# Driver.net
KiCad netlist of a schematic drawn in Altium Designer
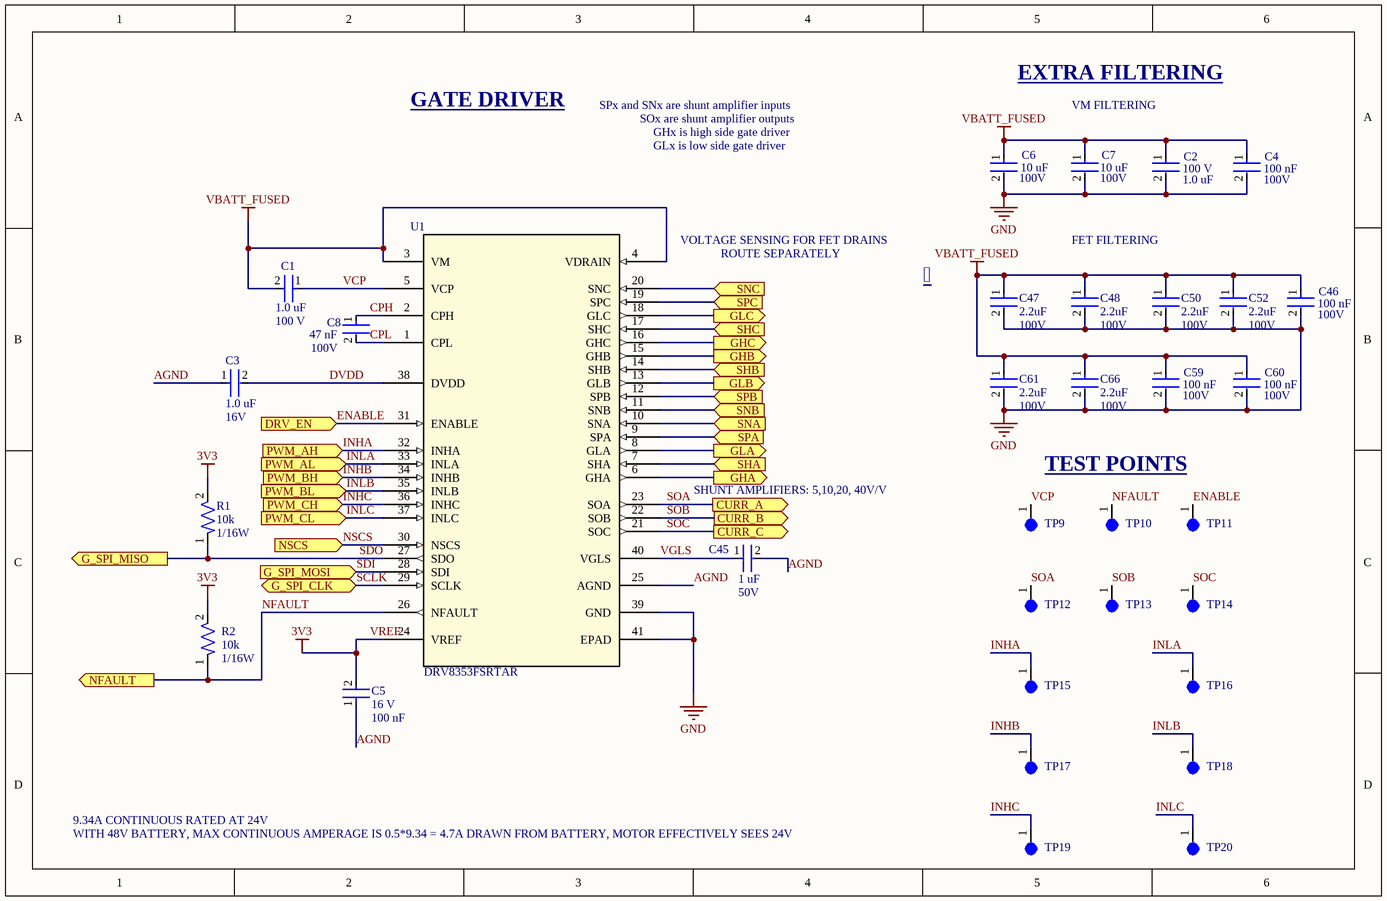
[diagram p0: Driver.SchDoc]

(export (version "E")
  (design (tool "Eeschema 10.0.6"))
  (components
    (comp (ref "C1")
      (value "08051C105K4Z2A")
      (footprint "CAP-0805")
      (description "CAP CER 1UF 50V X7R 0805")
      (fields (field (name "VOLTAGE") "100 V") (field (name "CAPACITANCE") "1.0 uF"))
      (libsource (lib "JLC_25") (part "CAP-1U-0001"))
    )
    (comp (ref "C2")
      (value "08051C105K4Z2A")
      (footprint "CAP-0805")
      (description "CAP CER 1UF 50V X7R 0805")
      (fields (field (name "VOLTAGE") "100 V") (field (name "CAPACITANCE") "1.0 uF"))
      (libsource (lib "JLC_25") (part "CAP-1U-0001"))
    )
    (comp (ref "C3")
      (value "CC0603KRX7R7BB105")
      (footprint "CAP-0603")
      (description "CAP CER 1UF 16V X7R 0603")
      (fields (field (name "CAPACITANCE") "1.0 uF") (field (name "VOLTAGE") "16V"))
      (libsource (lib "JLC_25") (part "CAP-1U-0002"))
    )
    (comp (ref "C4")
      (value "GRM188R72A104KA35D")
      (footprint "CAP-0603")
      (description "CAP CER 100NF 100V X7R 0603")
      (fields (field (name "CAPACITANCE") "100 nF") (field (name "VOLTAGE") "100V"))
      (libsource (lib "JLC_25") (part "CAP-1U-0002"))
    )
    (comp (ref "C5")
      (value "CC0402KRX7R7BB104")
      (footprint "CAP-0402")
      (description "CAP CER 0.1UF 16V X7R 0402")
      (fields (field (name "VOLTAGE RATING") "16 V") (field (name "CAPACITANCE") "100 nF"))
      (libsource (lib "JLC_25") (part "CAP-0.1U-0001"))
    )
    (comp (ref "C6")
      (value "GRM32EC72A106KE05L")
      (footprint "CAP-1210")
      (description "10 µF ±10% 100V Ceramic Capacitor X7S 1210 (3225 Metric)")
      (fields (field (name "CAPCITANCE") "10 uF") (field (name "VOLTAGE RATING") "100V"))
      (libsource (lib "MasterLib") (part "CAP-10U-0003"))
    )
    (comp (ref "C7")
      (value "GRM32EC72A106KE05L")
      (footprint "CAP-1210")
      (description "10 µF ±10% 100V Ceramic Capacitor X7S 1210 (3225 Metric)")
      (fields (field (name "CAPCITANCE") "10 uF") (field (name "VOLTAGE RATING") "100V"))
      (libsource (lib "MasterLib") (part "CAP-10U-0003"))
    )
    (comp (ref "C8")
      (value "C0603C473K1RACTU")
      (footprint "CAP-0603")
      (description "CAP CER 47NF 100V X5R 0603")
      (fields (field (name "CAPACITANCE") "47 nF") (field (name "VOLTAGE") "100V"))
      (libsource (lib "JLC_25") (part "CAP-4.7U-0001"))
    )
    (comp (ref "C45")
      (value "UMK107AB7105KA-T")
      (footprint "CAP-0603")
      (description "1 µF ±10% 50V Ceramic Capacitor X7R 0603 (1608 Metric)")
      (fields (field (name "CAPACITANCE") "1 uF") (field (name "VOLTAGE") "50V"))
      (libsource (lib "MasterLib") (part "CAP-1U-0002"))
    )
    (comp (ref "C46")
      (value "GRM188R72A104KA35D")
      (footprint "CAP-0603")
      (description "CAP CER 100NF 100V X7R 0603")
      (fields (field (name "CAPACITANCE") "100 nF") (field (name "VOLTAGE") "100V"))
      (libsource (lib "JLC_25") (part "CAP-1U-0002"))
    )
    (comp (ref "C47")
      (value "CC1206KKX7R0BB225")
      (footprint "CAP-1206")
      (description "CAP CER 2.2UF 100V X7R 1206")
      (fields (field (name "CAPACITANCE") "2.2uF") (field (name "VOLTAGE") "100V"))
      (libsource (lib "JLC_25") (part "CAP-2.2U-0001"))
    )
    (comp (ref "C48")
      (value "CC1206KKX7R0BB225")
      (footprint "CAP-1206")
      (description "CAP CER 2.2UF 100V X7R 1206")
      (fields (field (name "CAPACITANCE") "2.2uF") (field (name "VOLTAGE") "100V"))
      (libsource (lib "JLC_25") (part "CAP-2.2U-0001"))
    )
    (comp (ref "C50")
      (value "CC1206KKX7R0BB225")
      (footprint "CAP-1206")
      (description "CAP CER 2.2UF 100V X7R 1206")
      (fields (field (name "CAPACITANCE") "2.2uF") (field (name "VOLTAGE") "100V"))
      (libsource (lib "JLC_25") (part "CAP-2.2U-0001"))
    )
    (comp (ref "C52")
      (value "CC1206KKX7R0BB225")
      (footprint "CAP-1206")
      (description "CAP CER 2.2UF 100V X7R 1206")
      (fields (field (name "CAPACITANCE") "2.2uF") (field (name "VOLTAGE") "100V"))
      (libsource (lib "JLC_25") (part "CAP-2.2U-0001"))
    )
    (comp (ref "C59")
      (value "GRM188R72A104KA35D")
      (footprint "CAP-0603")
      (description "CAP CER 100NF 100V X7R 0603")
      (fields (field (name "CAPACITANCE") "100 nF") (field (name "VOLTAGE") "100V"))
      (libsource (lib "JLC_25") (part "CAP-1U-0002"))
    )
    (comp (ref "C60")
      (value "GRM188R72A104KA35D")
      (footprint "CAP-0603")
      (description "CAP CER 100NF 100V X7R 0603")
      (fields (field (name "CAPACITANCE") "100 nF") (field (name "VOLTAGE") "100V"))
      (libsource (lib "JLC_25") (part "CAP-1U-0002"))
    )
    (comp (ref "C61")
      (value "CC1206KKX7R0BB225")
      (footprint "CAP-1206")
      (description "CAP CER 2.2UF 100V X7R 1206")
      (fields (field (name "CAPACITANCE") "2.2uF") (field (name "VOLTAGE") "100V"))
      (libsource (lib "JLC_25") (part "CAP-2.2U-0001"))
    )
    (comp (ref "C66")
      (value "CC1206KKX7R0BB225")
      (footprint "CAP-1206")
      (description "CAP CER 2.2UF 100V X7R 1206")
      (fields (field (name "CAPACITANCE") "2.2uF") (field (name "VOLTAGE") "100V"))
      (libsource (lib "JLC_25") (part "CAP-2.2U-0001"))
    )
    (comp (ref "R1")
      (value "RC0402FR-0710KL")
      (footprint "RES-0402")
      (description "RES 10K OHM 1% 1/16W 0402")
      (fields
        (field (name "TOLERANCE") "1%")
        (field (name "RESISTANCE") "10k")
        (field (name "POWER") "1/16W")
      )
      (libsource (lib "JLC_25") (part "RES-10k-0001"))
    )
    (comp (ref "R2")
      (value "RC0402FR-0710KL")
      (footprint "RES-0402")
      (description "RES 10K OHM 1% 1/16W 0402")
      (fields
        (field (name "TOLERANCE") "1%")
        (field (name "RESISTANCE") "10k")
        (field (name "POWER") "1/16W")
      )
      (libsource (lib "JLC_25") (part "RES-10k-0001"))
    )
    (comp (ref "TP9")
      (value "5003")
      (footprint "TEST-POINT-0001")
      (description "Oranange PC Test Point, Miniature Phoisphor Bronze Silver Plating Through Hole Mounting Type")
      (libsource (lib "JLC_25") (part "TEST-POINT-0001"))
    )
    (comp (ref "TP10")
      (value "5003")
      (footprint "TEST-POINT-0001")
      (description "Oranange PC Test Point, Miniature Phoisphor Bronze Silver Plating Through Hole Mounting Type")
      (libsource (lib "JLC_25") (part "TEST-POINT-0001"))
    )
    (comp (ref "TP11")
      (value "5003")
      (footprint "TEST-POINT-0001")
      (description "Oranange PC Test Point, Miniature Phoisphor Bronze Silver Plating Through Hole Mounting Type")
      (libsource (lib "JLC_25") (part "TEST-POINT-0001"))
    )
    (comp (ref "TP12")
      (value "5003")
      (footprint "TEST-POINT-0001")
      (description "Oranange PC Test Point, Miniature Phoisphor Bronze Silver Plating Through Hole Mounting Type")
      (libsource (lib "JLC_25") (part "TEST-POINT-0001"))
    )
    (comp (ref "TP13")
      (value "5003")
      (footprint "TEST-POINT-0001")
      (description "Oranange PC Test Point, Miniature Phoisphor Bronze Silver Plating Through Hole Mounting Type")
      (libsource (lib "JLC_25") (part "TEST-POINT-0001"))
    )
    (comp (ref "TP14")
      (value "5003")
      (footprint "TEST-POINT-0001")
      (description "Oranange PC Test Point, Miniature Phoisphor Bronze Silver Plating Through Hole Mounting Type")
      (libsource (lib "JLC_25") (part "TEST-POINT-0001"))
    )
    (comp (ref "TP15")
      (value "5003")
      (footprint "TEST-POINT-0001")
      (description "Oranange PC Test Point, Miniature Phoisphor Bronze Silver Plating Through Hole Mounting Type")
      (libsource (lib "JLC_25") (part "TEST-POINT-0001"))
    )
    (comp (ref "TP16")
      (value "5003")
      (footprint "TEST-POINT-0001")
      (description "Oranange PC Test Point, Miniature Phoisphor Bronze Silver Plating Through Hole Mounting Type")
      (libsource (lib "JLC_25") (part "TEST-POINT-0001"))
    )
    (comp (ref "TP17")
      (value "5003")
      (footprint "TEST-POINT-0001")
      (description "Oranange PC Test Point, Miniature Phoisphor Bronze Silver Plating Through Hole Mounting Type")
      (libsource (lib "JLC_25") (part "TEST-POINT-0001"))
    )
    (comp (ref "TP18")
      (value "5003")
      (footprint "TEST-POINT-0001")
      (description "Oranange PC Test Point, Miniature Phoisphor Bronze Silver Plating Through Hole Mounting Type")
      (libsource (lib "JLC_25") (part "TEST-POINT-0001"))
    )
    (comp (ref "TP19")
      (value "5003")
      (footprint "TEST-POINT-0001")
      (description "Oranange PC Test Point, Miniature Phoisphor Bronze Silver Plating Through Hole Mounting Type")
      (libsource (lib "JLC_25") (part "TEST-POINT-0001"))
    )
    (comp (ref "TP20")
      (value "5003")
      (footprint "TEST-POINT-0001")
      (description "Oranange PC Test Point, Miniature Phoisphor Bronze Silver Plating Through Hole Mounting Type")
      (libsource (lib "JLC_25") (part "TEST-POINT-0001"))
    )
    (comp (ref "U1")
      (value "DRV8353FSRTAR")
      (footprint "IC-GDRV-0002")
      (description "102-V MAX 3-PHASE FUNCTIONAL SAF")
      (fields (field (name "COPYRIGHT") "Copyright (C) 2025 Ultra Librarian. All rights reserved."))
      (libsource (lib "MasterLib") (part "IC-GDRV-0002"))
    )
  )
  (nets
    (net (code "1") (name "/AGND") (class "Default")
      (node (ref "C3") (pin "1") (pinfunction "1_1") (pintype "passive"))
      (node (ref "C45") (pin "2") (pinfunction "2_2") (pintype "passive"))
      (node (ref "C5") (pin "1") (pinfunction "1_1") (pintype "passive"))
      (node (ref "U1") (pin "25") (pinfunction "AGND_25") (pintype "power_in"))
    )
    (net (code "2") (name "/CPH") (class "Default")
      (node (ref "C8") (pin "1") (pinfunction "1_1") (pintype "passive"))
      (node (ref "U1") (pin "2") (pinfunction "CPH_2") (pintype "power_in"))
    )
    (net (code "3") (name "/CPL") (class "Default")
      (node (ref "C8") (pin "2") (pinfunction "2_2") (pintype "passive"))
      (node (ref "U1") (pin "1") (pinfunction "CPL_1") (pintype "power_in"))
    )
    (net (code "4") (name "/DVDD") (class "Default")
      (node (ref "C3") (pin "2") (pinfunction "2_2") (pintype "passive"))
      (node (ref "U1") (pin "38") (pinfunction "DVDD_38") (pintype "power_in"))
    )
    (net (code "5") (name "/ENABLE") (class "Default")
      (node (ref "TP11") (pin "1") (pinfunction "0_1") (pintype "passive"))
      (node (ref "U1") (pin "31") (pinfunction "ENABLE_31") (pintype "input"))
    )
    (net (code "6") (name "/GHA") (class "Default")
      (node (ref "U1") (pin "6") (pinfunction "GHA_6") (pintype "output"))
    )
    (net (code "7") (name "/GHB") (class "Default")
      (node (ref "U1") (pin "15") (pinfunction "GHB_15") (pintype "output"))
    )
    (net (code "8") (name "/GHC") (class "Default")
      (node (ref "U1") (pin "16") (pinfunction "GHC_16") (pintype "output"))
    )
    (net (code "9") (name "/GLA") (class "Default")
      (node (ref "U1") (pin "8") (pinfunction "GLA_8") (pintype "output"))
    )
    (net (code "10") (name "/GLB") (class "Default")
      (node (ref "U1") (pin "13") (pinfunction "GLB_13") (pintype "output"))
    )
    (net (code "11") (name "/GLC") (class "Default")
      (node (ref "U1") (pin "18") (pinfunction "GLC_18") (pintype "output"))
    )
    (net (code "12") (name "/INHA") (class "Default")
      (node (ref "TP15") (pin "1") (pinfunction "0_1") (pintype "passive"))
      (node (ref "U1") (pin "32") (pinfunction "INHA_32") (pintype "input"))
    )
    (net (code "13") (name "/INHB") (class "Default")
      (node (ref "TP17") (pin "1") (pinfunction "0_1") (pintype "passive"))
      (node (ref "U1") (pin "34") (pinfunction "INHB_34") (pintype "input"))
    )
    (net (code "14") (name "/INHC") (class "Default")
      (node (ref "TP19") (pin "1") (pinfunction "0_1") (pintype "passive"))
      (node (ref "U1") (pin "36") (pinfunction "INHC_36") (pintype "input"))
    )
    (net (code "15") (name "/INLA") (class "Default")
      (node (ref "TP16") (pin "1") (pinfunction "0_1") (pintype "passive"))
      (node (ref "U1") (pin "33") (pinfunction "INLA_33") (pintype "input"))
    )
    (net (code "16") (name "/INLB") (class "Default")
      (node (ref "TP18") (pin "1") (pinfunction "0_1") (pintype "passive"))
      (node (ref "U1") (pin "35") (pinfunction "INLB_35") (pintype "input"))
    )
    (net (code "17") (name "/INLC") (class "Default")
      (node (ref "TP20") (pin "1") (pinfunction "0_1") (pintype "passive"))
      (node (ref "U1") (pin "37") (pinfunction "INLC_37") (pintype "input"))
    )
    (net (code "18") (name "/NFAULT") (class "Default")
      (node (ref "R2") (pin "1") (pinfunction "1_1") (pintype "passive"))
      (node (ref "TP10") (pin "1") (pinfunction "0_1") (pintype "passive"))
      (node (ref "U1") (pin "26") (pinfunction "NFAULT_26") (pintype "output"))
    )
    (net (code "19") (name "/NSCS") (class "Default")
      (node (ref "U1") (pin "30") (pinfunction "NSCS_30") (pintype "input"))
    )
    (net (code "20") (name "/SCLK") (class "Default")
      (node (ref "U1") (pin "29") (pinfunction "SCLK_29") (pintype "input"))
    )
    (net (code "21") (name "/SDI") (class "Default")
      (node (ref "U1") (pin "28") (pinfunction "SDI_28") (pintype "input"))
    )
    (net (code "22") (name "/SDO") (class "Default")
      (node (ref "R1") (pin "1") (pinfunction "1_1") (pintype "passive"))
      (node (ref "U1") (pin "27") (pinfunction "SDO_27") (pintype "output"))
    )
    (net (code "23") (name "/SHA") (class "Default")
      (node (ref "U1") (pin "7") (pinfunction "SHA_7") (pintype "input"))
    )
    (net (code "24") (name "/SHB") (class "Default")
      (node (ref "U1") (pin "14") (pinfunction "SHB_14") (pintype "input"))
    )
    (net (code "25") (name "/SHC") (class "Default")
      (node (ref "U1") (pin "17") (pinfunction "SHC_17") (pintype "input"))
    )
    (net (code "26") (name "/SNA") (class "Default")
      (node (ref "U1") (pin "10") (pinfunction "SNA_10") (pintype "input"))
    )
    (net (code "27") (name "/SNB") (class "Default")
      (node (ref "U1") (pin "11") (pinfunction "SNB_11") (pintype "input"))
    )
    (net (code "28") (name "/SNC") (class "Default")
      (node (ref "U1") (pin "20") (pinfunction "SNC_20") (pintype "input"))
    )
    (net (code "29") (name "/SOA") (class "Default")
      (node (ref "TP12") (pin "1") (pinfunction "0_1") (pintype "passive"))
      (node (ref "U1") (pin "23") (pinfunction "SOA_23") (pintype "output"))
    )
    (net (code "30") (name "/SOB") (class "Default")
      (node (ref "TP13") (pin "1") (pinfunction "0_1") (pintype "passive"))
      (node (ref "U1") (pin "22") (pinfunction "SOB_22") (pintype "output"))
    )
    (net (code "31") (name "/SOC") (class "Default")
      (node (ref "TP14") (pin "1") (pinfunction "0_1") (pintype "passive"))
      (node (ref "U1") (pin "21") (pinfunction "SOC_21") (pintype "output"))
    )
    (net (code "32") (name "/SPA") (class "Default")
      (node (ref "U1") (pin "9") (pinfunction "SPA_9") (pintype "input"))
    )
    (net (code "33") (name "/SPB") (class "Default")
      (node (ref "U1") (pin "12") (pinfunction "SPB_12") (pintype "input"))
    )
    (net (code "34") (name "/SPC") (class "Default")
      (node (ref "U1") (pin "19") (pinfunction "SPC_19") (pintype "input"))
    )
    (net (code "35") (name "/VCP") (class "Default")
      (node (ref "C1") (pin "1") (pinfunction "1_1") (pintype "passive"))
      (node (ref "TP9") (pin "1") (pinfunction "0_1") (pintype "passive"))
      (node (ref "U1") (pin "5") (pinfunction "VCP_5") (pintype "power_in"))
    )
    (net (code "36") (name "/VGLS") (class "Default")
      (node (ref "C45") (pin "1") (pinfunction "1_1") (pintype "passive"))
      (node (ref "U1") (pin "40") (pinfunction "VGLS_40") (pintype "power_in"))
    )
    (net (code "37") (name "3V3") (class "Default")
      (node (ref "C5") (pin "2") (pinfunction "2_2") (pintype "passive"))
      (node (ref "R1") (pin "2") (pinfunction "2_2") (pintype "passive"))
      (node (ref "R2") (pin "2") (pinfunction "2_2") (pintype "passive"))
      (node (ref "U1") (pin "24") (pinfunction "VREF_24") (pintype "power_in"))
    )
    (net (code "38") (name "GND") (class "Default")
      (node (ref "C2") (pin "2") (pinfunction "2_2") (pintype "passive"))
      (node (ref "C4") (pin "2") (pinfunction "2_2") (pintype "passive"))
      (node (ref "C46") (pin "2") (pinfunction "2_2") (pintype "passive"))
      (node (ref "C47") (pin "2") (pinfunction "2_2") (pintype "passive"))
      (node (ref "C48") (pin "2") (pinfunction "2_2") (pintype "passive"))
      (node (ref "C50") (pin "2") (pinfunction "2_2") (pintype "passive"))
      (node (ref "C52") (pin "2") (pinfunction "2_2") (pintype "passive"))
      (node (ref "C59") (pin "2") (pinfunction "2_2") (pintype "passive"))
      (node (ref "C6") (pin "2") (pinfunction "2_2") (pintype "passive"))
      (node (ref "C60") (pin "2") (pinfunction "2_2") (pintype "passive"))
      (node (ref "C61") (pin "2") (pinfunction "2_2") (pintype "passive"))
      (node (ref "C66") (pin "2") (pinfunction "2_2") (pintype "passive"))
      (node (ref "C7") (pin "2") (pinfunction "2_2") (pintype "passive"))
      (node (ref "U1") (pin "39") (pinfunction "GND_39") (pintype "power_in"))
      (node (ref "U1") (pin "41") (pinfunction "EPAD_41") (pintype "power_in"))
    )
    (net (code "39") (name "VBATT_FUSED") (class "Default")
      (node (ref "C1") (pin "2") (pinfunction "2_2") (pintype "passive"))
      (node (ref "C2") (pin "1") (pinfunction "1_1") (pintype "passive"))
      (node (ref "C4") (pin "1") (pinfunction "1_1") (pintype "passive"))
      (node (ref "C46") (pin "1") (pinfunction "1_1") (pintype "passive"))
      (node (ref "C47") (pin "1") (pinfunction "1_1") (pintype "passive"))
      (node (ref "C48") (pin "1") (pinfunction "1_1") (pintype "passive"))
      (node (ref "C50") (pin "1") (pinfunction "1_1") (pintype "passive"))
      (node (ref "C52") (pin "1") (pinfunction "1_1") (pintype "passive"))
      (node (ref "C59") (pin "1") (pinfunction "1_1") (pintype "passive"))
      (node (ref "C6") (pin "1") (pinfunction "1_1") (pintype "passive"))
      (node (ref "C60") (pin "1") (pinfunction "1_1") (pintype "passive"))
      (node (ref "C61") (pin "1") (pinfunction "1_1") (pintype "passive"))
      (node (ref "C66") (pin "1") (pinfunction "1_1") (pintype "passive"))
      (node (ref "C7") (pin "1") (pinfunction "1_1") (pintype "passive"))
      (node (ref "U1") (pin "3") (pinfunction "VM_3") (pintype "power_in"))
      (node (ref "U1") (pin "4") (pinfunction "VDRAIN_4") (pintype "input"))
    )
  )
)
